# DRS4_GPIO_EXPANDER.net
KiCad netlist of a schematic drawn in Altium Designer
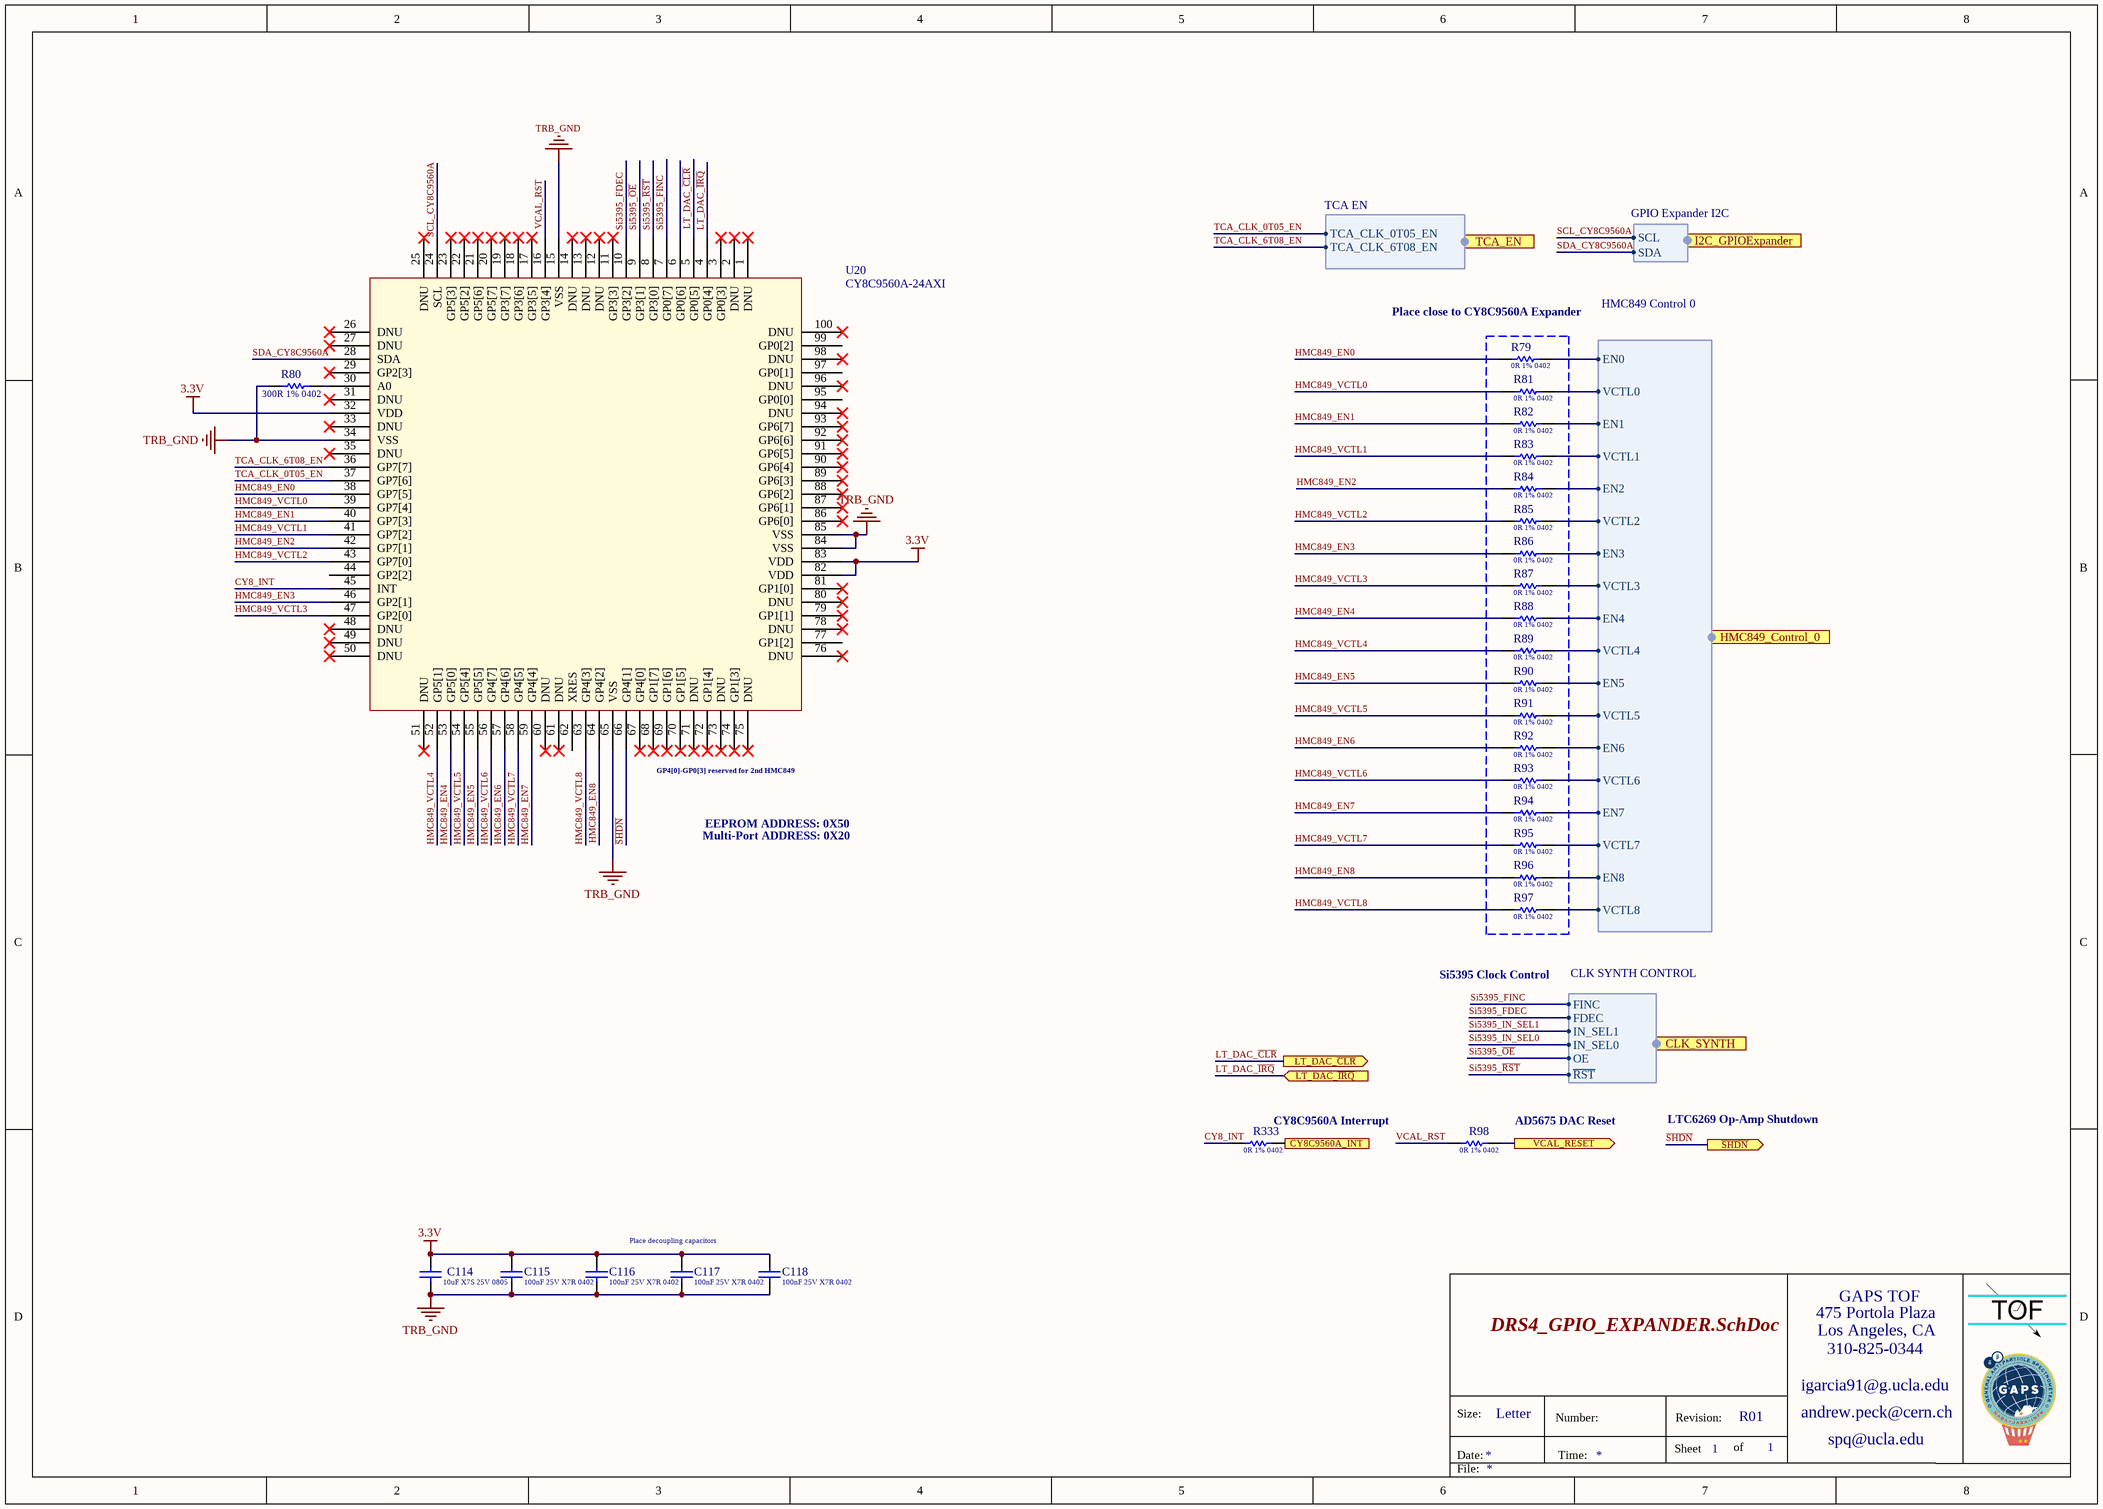
[diagram p0: DRS4_GPIO_EXPANDER.SchDoc]

(export (version "E")
  (design (tool "Eeschema 10.0.6"))
  (components
    (comp (ref "C114")
      (value "Cap_Murata_ GRM21BC71E106ME11L_10uF")
      (footprint "Cap_Murata_ GRM21BC71E106ME11L_10uF")
      (description "CAP CER 10uF 25V X7R 0805")
      (fields (field (name "CAPACITANCE") "10uF X7S 25V 0805"))
      (libsource (lib "Cap_Murata_ GRM21BC71E106ME11L_10uF") (part "Cap_Murata_ GRM21BC71E106ME11L_10uF"))
    )
    (comp (ref "C115")
      (value "Cap_Taiyo_Yuden_TMK105B7104KV-FR_100nF")
      (footprint "Cap_Taiyo_Yuden_TMK105B7104KV-FR_100nF")
      (description "CAP CER 100nF 25V X7R 0402")
      (fields (field (name "CAPACITANCE") "100nF 25V X7R 0402"))
      (libsource (lib "Cap_Taiyo_Yuden_TMK105B7104KV-FR_100nF") (part "Cap_Taiyo_Yuden_TMK105B7104KV-FR_100nF"))
    )
    (comp (ref "C116")
      (value "Cap_Taiyo_Yuden_TMK105B7104KV-FR_100nF")
      (footprint "Cap_Taiyo_Yuden_TMK105B7104KV-FR_100nF")
      (description "CAP CER 100nF 25V X7R 0402")
      (fields (field (name "CAPACITANCE") "100nF 25V X7R 0402"))
      (libsource (lib "Cap_Taiyo_Yuden_TMK105B7104KV-FR_100nF") (part "Cap_Taiyo_Yuden_TMK105B7104KV-FR_100nF"))
    )
    (comp (ref "C117")
      (value "Cap_Taiyo_Yuden_TMK105B7104KV-FR_100nF")
      (footprint "Cap_Taiyo_Yuden_TMK105B7104KV-FR_100nF")
      (description "CAP CER 100nF 25V X7R 0402")
      (fields (field (name "CAPACITANCE") "100nF 25V X7R 0402"))
      (libsource (lib "Cap_Taiyo_Yuden_TMK105B7104KV-FR_100nF") (part "Cap_Taiyo_Yuden_TMK105B7104KV-FR_100nF"))
    )
    (comp (ref "C118")
      (value "Cap_Taiyo_Yuden_TMK105B7104KV-FR_100nF")
      (footprint "Cap_Taiyo_Yuden_TMK105B7104KV-FR_100nF")
      (description "CAP CER 100nF 25V X7R 0402")
      (fields (field (name "CAPACITANCE") "100nF 25V X7R 0402"))
      (libsource (lib "Cap_Taiyo_Yuden_TMK105B7104KV-FR_100nF") (part "Cap_Taiyo_Yuden_TMK105B7104KV-FR_100nF"))
    )
    (comp (ref "R79")
      (value "Res_Vishay_CRCW04020000Z0EDC_0_Ohm")
      (footprint "Res_Vishay_CRCW04020000Z0EDC_0_Ohm")
      (description "0R 0.062W 1% 0402 (1005 Metric)  SMD")
      (fields (field (name "RESISTANCE") "0R 1% 0402"))
      (libsource (lib "Res_Vishay_CRCW04020000Z0EDC_0_Ohm") (part "Res_Vishay_CRCW04020000Z0EDC_0_Ohm"))
    )
    (comp (ref "R80")
      (value "300R 1% 0402")
      (footprint "RESC0402(1005)_L")
      (description "300R 0.063W 1% 0402 (1005 Metric)  SMD")
      (fields (field (name "TOLERANCE") "1 %") (field (name "POWER") "0.063 W"))
      (libsource (lib "Altium Content Vault") (part "RES"))
    )
    (comp (ref "R81")
      (value "Res_Vishay_CRCW04020000Z0EDC_0_Ohm")
      (footprint "Res_Vishay_CRCW04020000Z0EDC_0_Ohm")
      (description "0R 0.062W 1% 0402 (1005 Metric)  SMD")
      (fields (field (name "RESISTANCE") "0R 1% 0402"))
      (libsource (lib "Res_Vishay_CRCW04020000Z0EDC_0_Ohm") (part "Res_Vishay_CRCW04020000Z0EDC_0_Ohm"))
    )
    (comp (ref "R82")
      (value "Res_Vishay_CRCW04020000Z0EDC_0_Ohm")
      (footprint "Res_Vishay_CRCW04020000Z0EDC_0_Ohm")
      (description "0R 0.062W 1% 0402 (1005 Metric)  SMD")
      (fields (field (name "RESISTANCE") "0R 1% 0402"))
      (libsource (lib "Res_Vishay_CRCW04020000Z0EDC_0_Ohm") (part "Res_Vishay_CRCW04020000Z0EDC_0_Ohm"))
    )
    (comp (ref "R83")
      (value "Res_Vishay_CRCW04020000Z0EDC_0_Ohm")
      (footprint "Res_Vishay_CRCW04020000Z0EDC_0_Ohm")
      (description "0R 0.062W 1% 0402 (1005 Metric)  SMD")
      (fields (field (name "RESISTANCE") "0R 1% 0402"))
      (libsource (lib "Res_Vishay_CRCW04020000Z0EDC_0_Ohm") (part "Res_Vishay_CRCW04020000Z0EDC_0_Ohm"))
    )
    (comp (ref "R84")
      (value "Res_Vishay_CRCW04020000Z0EDC_0_Ohm")
      (footprint "Res_Vishay_CRCW04020000Z0EDC_0_Ohm")
      (description "0R 0.062W 1% 0402 (1005 Metric)  SMD")
      (fields (field (name "RESISTANCE") "0R 1% 0402"))
      (libsource (lib "Res_Vishay_CRCW04020000Z0EDC_0_Ohm") (part "Res_Vishay_CRCW04020000Z0EDC_0_Ohm"))
    )
    (comp (ref "R85")
      (value "Res_Vishay_CRCW04020000Z0EDC_0_Ohm")
      (footprint "Res_Vishay_CRCW04020000Z0EDC_0_Ohm")
      (description "0R 0.062W 1% 0402 (1005 Metric)  SMD")
      (fields (field (name "RESISTANCE") "0R 1% 0402"))
      (libsource (lib "Res_Vishay_CRCW04020000Z0EDC_0_Ohm") (part "Res_Vishay_CRCW04020000Z0EDC_0_Ohm"))
    )
    (comp (ref "R86")
      (value "Res_Vishay_CRCW04020000Z0EDC_0_Ohm")
      (footprint "Res_Vishay_CRCW04020000Z0EDC_0_Ohm")
      (description "0R 0.062W 1% 0402 (1005 Metric)  SMD")
      (fields (field (name "RESISTANCE") "0R 1% 0402"))
      (libsource (lib "Res_Vishay_CRCW04020000Z0EDC_0_Ohm") (part "Res_Vishay_CRCW04020000Z0EDC_0_Ohm"))
    )
    (comp (ref "R87")
      (value "Res_Vishay_CRCW04020000Z0EDC_0_Ohm")
      (footprint "Res_Vishay_CRCW04020000Z0EDC_0_Ohm")
      (description "0R 0.062W 1% 0402 (1005 Metric)  SMD")
      (fields (field (name "RESISTANCE") "0R 1% 0402"))
      (libsource (lib "Res_Vishay_CRCW04020000Z0EDC_0_Ohm") (part "Res_Vishay_CRCW04020000Z0EDC_0_Ohm"))
    )
    (comp (ref "R88")
      (value "Res_Vishay_CRCW04020000Z0EDC_0_Ohm")
      (footprint "Res_Vishay_CRCW04020000Z0EDC_0_Ohm")
      (description "0R 0.062W 1% 0402 (1005 Metric)  SMD")
      (fields (field (name "RESISTANCE") "0R 1% 0402"))
      (libsource (lib "Res_Vishay_CRCW04020000Z0EDC_0_Ohm") (part "Res_Vishay_CRCW04020000Z0EDC_0_Ohm"))
    )
    (comp (ref "R89")
      (value "Res_Vishay_CRCW04020000Z0EDC_0_Ohm")
      (footprint "Res_Vishay_CRCW04020000Z0EDC_0_Ohm")
      (description "0R 0.062W 1% 0402 (1005 Metric)  SMD")
      (fields (field (name "RESISTANCE") "0R 1% 0402"))
      (libsource (lib "Res_Vishay_CRCW04020000Z0EDC_0_Ohm") (part "Res_Vishay_CRCW04020000Z0EDC_0_Ohm"))
    )
    (comp (ref "R90")
      (value "Res_Vishay_CRCW04020000Z0EDC_0_Ohm")
      (footprint "Res_Vishay_CRCW04020000Z0EDC_0_Ohm")
      (description "0R 0.062W 1% 0402 (1005 Metric)  SMD")
      (fields (field (name "RESISTANCE") "0R 1% 0402"))
      (libsource (lib "Res_Vishay_CRCW04020000Z0EDC_0_Ohm") (part "Res_Vishay_CRCW04020000Z0EDC_0_Ohm"))
    )
    (comp (ref "R91")
      (value "Res_Vishay_CRCW04020000Z0EDC_0_Ohm")
      (footprint "Res_Vishay_CRCW04020000Z0EDC_0_Ohm")
      (description "0R 0.062W 1% 0402 (1005 Metric)  SMD")
      (fields (field (name "RESISTANCE") "0R 1% 0402"))
      (libsource (lib "Res_Vishay_CRCW04020000Z0EDC_0_Ohm") (part "Res_Vishay_CRCW04020000Z0EDC_0_Ohm"))
    )
    (comp (ref "R92")
      (value "Res_Vishay_CRCW04020000Z0EDC_0_Ohm")
      (footprint "Res_Vishay_CRCW04020000Z0EDC_0_Ohm")
      (description "0R 0.062W 1% 0402 (1005 Metric)  SMD")
      (fields (field (name "RESISTANCE") "0R 1% 0402"))
      (libsource (lib "Res_Vishay_CRCW04020000Z0EDC_0_Ohm") (part "Res_Vishay_CRCW04020000Z0EDC_0_Ohm"))
    )
    (comp (ref "R93")
      (value "Res_Vishay_CRCW04020000Z0EDC_0_Ohm")
      (footprint "Res_Vishay_CRCW04020000Z0EDC_0_Ohm")
      (description "0R 0.062W 1% 0402 (1005 Metric)  SMD")
      (fields (field (name "RESISTANCE") "0R 1% 0402"))
      (libsource (lib "Res_Vishay_CRCW04020000Z0EDC_0_Ohm") (part "Res_Vishay_CRCW04020000Z0EDC_0_Ohm"))
    )
    (comp (ref "R94")
      (value "Res_Vishay_CRCW04020000Z0EDC_0_Ohm")
      (footprint "Res_Vishay_CRCW04020000Z0EDC_0_Ohm")
      (description "0R 0.062W 1% 0402 (1005 Metric)  SMD")
      (fields (field (name "RESISTANCE") "0R 1% 0402"))
      (libsource (lib "Res_Vishay_CRCW04020000Z0EDC_0_Ohm") (part "Res_Vishay_CRCW04020000Z0EDC_0_Ohm"))
    )
    (comp (ref "R95")
      (value "Res_Vishay_CRCW04020000Z0EDC_0_Ohm")
      (footprint "Res_Vishay_CRCW04020000Z0EDC_0_Ohm")
      (description "0R 0.062W 1% 0402 (1005 Metric)  SMD")
      (fields (field (name "RESISTANCE") "0R 1% 0402"))
      (libsource (lib "Res_Vishay_CRCW04020000Z0EDC_0_Ohm") (part "Res_Vishay_CRCW04020000Z0EDC_0_Ohm"))
    )
    (comp (ref "R96")
      (value "Res_Vishay_CRCW04020000Z0EDC_0_Ohm")
      (footprint "Res_Vishay_CRCW04020000Z0EDC_0_Ohm")
      (description "0R 0.062W 1% 0402 (1005 Metric)  SMD")
      (fields (field (name "RESISTANCE") "0R 1% 0402"))
      (libsource (lib "Res_Vishay_CRCW04020000Z0EDC_0_Ohm") (part "Res_Vishay_CRCW04020000Z0EDC_0_Ohm"))
    )
    (comp (ref "R97")
      (value "Res_Vishay_CRCW04020000Z0EDC_0_Ohm")
      (footprint "Res_Vishay_CRCW04020000Z0EDC_0_Ohm")
      (description "0R 0.062W 1% 0402 (1005 Metric)  SMD")
      (fields (field (name "RESISTANCE") "0R 1% 0402"))
      (libsource (lib "Res_Vishay_CRCW04020000Z0EDC_0_Ohm") (part "Res_Vishay_CRCW04020000Z0EDC_0_Ohm"))
    )
    (comp (ref "R98")
      (value "Res_Vishay_CRCW04020000Z0EDC_0_Ohm")
      (footprint "Res_Vishay_CRCW04020000Z0EDC_0_Ohm")
      (description "0R 0.062W 1% 0402 (1005 Metric)  SMD")
      (fields (field (name "RESISTANCE") "0R 1% 0402"))
      (libsource (lib "Res_Vishay_CRCW04020000Z0EDC_0_Ohm") (part "Res_Vishay_CRCW04020000Z0EDC_0_Ohm"))
    )
    (comp (ref "R333")
      (value "Res_Vishay_CRCW04020000Z0EDC_0_Ohm")
      (footprint "Res_Vishay_CRCW04020000Z0EDC_0_Ohm")
      (description "0R 0.062W 1% 0402 (1005 Metric)  SMD")
      (fields (field (name "RESISTANCE") "0R 1% 0402"))
      (libsource (lib "Res_Vishay_CRCW04020000Z0EDC_0_Ohm") (part "Res_Vishay_CRCW04020000Z0EDC_0_Ohm"))
    )
    (comp (ref "U20")
      (value "IC_Cypress_Semiconductor_CY8C9560A-24AXI")
      (footprint "IC_Cypress_Semiconductor_CY8C9560A-24AXI")
      (description "Interface - I/O Expanders 60BIT IO EXPANDER W/EEPROM")
      (fields (field (name "SERIES") "CY8C9560A-24AXI"))
      (libsource (lib "IC_Cypress_Semiconductor_CY8C9560A-24AXI") (part "IC_Cypress_Semiconductor_CY8C9560A-24AXI"))
    )
  )
  (nets
    (net (code "12") (name "/CY8C9560A_INT") (class "Default")
      (node (ref "R333") (pin "1") (pinfunction "1_1") (pintype "passive"))
    )
    (net (code "13") (name "/CY8_INT") (class "Default")
      (node (ref "R333") (pin "2") (pinfunction "2_2") (pintype "passive"))
      (node (ref "U20") (pin "45") (pinfunction "INT_45") (pintype "passive"))
    )
    (net (code "14") (name "/EN0") (class "Default")
      (node (ref "R79") (pin "2") (pinfunction "2_2") (pintype "passive"))
    )
    (net (code "15") (name "/EN1") (class "Default")
      (node (ref "R82") (pin "2") (pinfunction "2_2") (pintype "passive"))
    )
    (net (code "16") (name "/EN2") (class "Default")
      (node (ref "R84") (pin "2") (pinfunction "2_2") (pintype "passive"))
    )
    (net (code "17") (name "/EN3") (class "Default")
      (node (ref "R86") (pin "2") (pinfunction "2_2") (pintype "passive"))
    )
    (net (code "18") (name "/EN4") (class "Default")
      (node (ref "R88") (pin "2") (pinfunction "2_2") (pintype "passive"))
    )
    (net (code "19") (name "/EN5") (class "Default")
      (node (ref "R90") (pin "2") (pinfunction "2_2") (pintype "passive"))
    )
    (net (code "20") (name "/EN6") (class "Default")
      (node (ref "R92") (pin "2") (pinfunction "2_2") (pintype "passive"))
    )
    (net (code "21") (name "/EN7") (class "Default")
      (node (ref "R94") (pin "2") (pinfunction "2_2") (pintype "passive"))
    )
    (net (code "22") (name "/EN8") (class "Default")
      (node (ref "R96") (pin "2") (pinfunction "2_2") (pintype "passive"))
    )
    (net (code "23") (name "/HMC849_EN0") (class "Default")
      (node (ref "R79") (pin "1") (pinfunction "1_1") (pintype "passive"))
      (node (ref "U20") (pin "38") (pinfunction "GP7[5]_38") (pintype "passive"))
    )
    (net (code "24") (name "/HMC849_EN1") (class "Default")
      (node (ref "R82") (pin "1") (pinfunction "1_1") (pintype "passive"))
      (node (ref "U20") (pin "40") (pinfunction "GP7[3]_40") (pintype "passive"))
    )
    (net (code "25") (name "/HMC849_EN2") (class "Default")
      (node (ref "R84") (pin "1") (pinfunction "1_1") (pintype "passive"))
      (node (ref "U20") (pin "42") (pinfunction "GP7[1]_42") (pintype "passive"))
    )
    (net (code "26") (name "/HMC849_EN3") (class "Default")
      (node (ref "R86") (pin "1") (pinfunction "1_1") (pintype "passive"))
      (node (ref "U20") (pin "46") (pinfunction "GP2[1]_46") (pintype "passive"))
    )
    (net (code "27") (name "/HMC849_EN4") (class "Default")
      (node (ref "R88") (pin "1") (pinfunction "1_1") (pintype "passive"))
      (node (ref "U20") (pin "53") (pinfunction "GP5[0]_53") (pintype "passive"))
    )
    (net (code "28") (name "/HMC849_EN5") (class "Default")
      (node (ref "R90") (pin "1") (pinfunction "1_1") (pintype "passive"))
      (node (ref "U20") (pin "55") (pinfunction "GP5[5]_55") (pintype "passive"))
    )
    (net (code "29") (name "/HMC849_EN6") (class "Default")
      (node (ref "R92") (pin "1") (pinfunction "1_1") (pintype "passive"))
      (node (ref "U20") (pin "57") (pinfunction "GP4[6]_57") (pintype "passive"))
    )
    (net (code "30") (name "/HMC849_EN7") (class "Default")
      (node (ref "R94") (pin "1") (pinfunction "1_1") (pintype "passive"))
      (node (ref "U20") (pin "59") (pinfunction "GP4[4]_59") (pintype "passive"))
    )
    (net (code "31") (name "/HMC849_EN8") (class "Default")
      (node (ref "R96") (pin "1") (pinfunction "1_1") (pintype "passive"))
      (node (ref "U20") (pin "64") (pinfunction "GP4[2]_64") (pintype "passive"))
    )
    (net (code "32") (name "/HMC849_VCTL0") (class "Default")
      (node (ref "R81") (pin "1") (pinfunction "1_1") (pintype "passive"))
      (node (ref "U20") (pin "39") (pinfunction "GP7[4]_39") (pintype "passive"))
    )
    (net (code "33") (name "/HMC849_VCTL1") (class "Default")
      (node (ref "R83") (pin "1") (pinfunction "1_1") (pintype "passive"))
      (node (ref "U20") (pin "41") (pinfunction "GP7[2]_41") (pintype "passive"))
    )
    (net (code "34") (name "/HMC849_VCTL2") (class "Default")
      (node (ref "R85") (pin "1") (pinfunction "1_1") (pintype "passive"))
      (node (ref "U20") (pin "43") (pinfunction "GP7[0]_43") (pintype "passive"))
    )
    (net (code "35") (name "/HMC849_VCTL3") (class "Default")
      (node (ref "R87") (pin "1") (pinfunction "1_1") (pintype "passive"))
      (node (ref "U20") (pin "47") (pinfunction "GP2[0]_47") (pintype "passive"))
    )
    (net (code "36") (name "/HMC849_VCTL4") (class "Default")
      (node (ref "R89") (pin "1") (pinfunction "1_1") (pintype "passive"))
      (node (ref "U20") (pin "52") (pinfunction "GP5[1]_52") (pintype "passive"))
    )
    (net (code "37") (name "/HMC849_VCTL5") (class "Default")
      (node (ref "R91") (pin "1") (pinfunction "1_1") (pintype "passive"))
      (node (ref "U20") (pin "54") (pinfunction "GP5[4]_54") (pintype "passive"))
    )
    (net (code "38") (name "/HMC849_VCTL6") (class "Default")
      (node (ref "R93") (pin "1") (pinfunction "1_1") (pintype "passive"))
      (node (ref "U20") (pin "56") (pinfunction "GP4[7]_56") (pintype "passive"))
    )
    (net (code "39") (name "/HMC849_VCTL7") (class "Default")
      (node (ref "R95") (pin "1") (pinfunction "1_1") (pintype "passive"))
      (node (ref "U20") (pin "58") (pinfunction "GP4[5]_58") (pintype "passive"))
    )
    (net (code "40") (name "/HMC849_VCTL8") (class "Default")
      (node (ref "R97") (pin "1") (pinfunction "1_1") (pintype "passive"))
      (node (ref "U20") (pin "63") (pinfunction "GP4[3]_63") (pintype "passive"))
    )
    (net (code "41") (name "/LT_DAC_~{CLR}") (class "Default")
      (node (ref "U20") (pin "5") (pinfunction "GP0[5]_5") (pintype "passive"))
    )
    (net (code "42") (name "/LT_DAC_~{IRQ}") (class "Default")
      (node (ref "U20") (pin "4") (pinfunction "GP0[4]_4") (pintype "passive"))
    )
    (net (code "43") (name "/SCL_CY8C9560A") (class "Default")
      (node (ref "U20") (pin "24") (pinfunction "SCL_24") (pintype "passive"))
    )
    (net (code "44") (name "/SDA_CY8C9560A") (class "Default")
      (node (ref "U20") (pin "28") (pinfunction "SDA_28") (pintype "passive"))
    )
    (net (code "45") (name "/Si5395_FDEC") (class "Default")
      (node (ref "U20") (pin "10") (pinfunction "GP3[2]_10") (pintype "passive"))
    )
    (net (code "46") (name "/Si5395_FINC") (class "Default")
      (node (ref "U20") (pin "7") (pinfunction "GP0[7]_7") (pintype "passive"))
    )
    (net (code "49") (name "/Si5395_~{OE}") (class "Default")
      (node (ref "U20") (pin "9") (pinfunction "GP3[1]_9") (pintype "passive"))
    )
    (net (code "50") (name "/Si5395_~{RST}") (class "Default")
      (node (ref "U20") (pin "8") (pinfunction "GP3[0]_8") (pintype "passive"))
    )
    (net (code "51") (name "/TCA_CLK_0T05_EN") (class "Default")
      (node (ref "U20") (pin "37") (pinfunction "GP7[6]_37") (pintype "passive"))
    )
    (net (code "52") (name "/TCA_CLK_6T08_EN") (class "Default")
      (node (ref "U20") (pin "36") (pinfunction "GP7[7]_36") (pintype "passive"))
    )
    (net (code "53") (name "/VCAL_RESET") (class "Default")
      (node (ref "R98") (pin "1") (pinfunction "1_1") (pintype "passive"))
    )
    (net (code "54") (name "/VCAL_RST") (class "Default")
      (node (ref "R98") (pin "2") (pinfunction "2_2") (pintype "passive"))
      (node (ref "U20") (pin "16") (pinfunction "GP3[4]_16") (pintype "passive"))
    )
    (net (code "55") (name "/VCTL0") (class "Default")
      (node (ref "R81") (pin "2") (pinfunction "2_2") (pintype "passive"))
    )
    (net (code "56") (name "/VCTL1") (class "Default")
      (node (ref "R83") (pin "2") (pinfunction "2_2") (pintype "passive"))
    )
    (net (code "57") (name "/VCTL2") (class "Default")
      (node (ref "R85") (pin "2") (pinfunction "2_2") (pintype "passive"))
    )
    (net (code "58") (name "/VCTL3") (class "Default")
      (node (ref "R87") (pin "2") (pinfunction "2_2") (pintype "passive"))
    )
    (net (code "59") (name "/VCTL4") (class "Default")
      (node (ref "R89") (pin "2") (pinfunction "2_2") (pintype "passive"))
    )
    (net (code "60") (name "/VCTL5") (class "Default")
      (node (ref "R91") (pin "2") (pinfunction "2_2") (pintype "passive"))
    )
    (net (code "61") (name "/VCTL6") (class "Default")
      (node (ref "R93") (pin "2") (pinfunction "2_2") (pintype "passive"))
    )
    (net (code "62") (name "/VCTL7") (class "Default")
      (node (ref "R95") (pin "2") (pinfunction "2_2") (pintype "passive"))
    )
    (net (code "63") (name "/VCTL8") (class "Default")
      (node (ref "R97") (pin "2") (pinfunction "2_2") (pintype "passive"))
    )
    (net (code "68") (name "/~{SHDN}") (class "Default")
      (node (ref "U20") (pin "66") (pinfunction "GP4[1]_66") (pintype "passive"))
    )
    (net (code "69") (name "3.3V") (class "Default")
      (node (ref "C114") (pin "1") (pinfunction "1_1") (pintype "passive"))
      (node (ref "C115") (pin "2") (pinfunction "2_2") (pintype "passive"))
      (node (ref "C116") (pin "2") (pinfunction "2_2") (pintype "passive"))
      (node (ref "C117") (pin "2") (pinfunction "2_2") (pintype "passive"))
      (node (ref "C118") (pin "2") (pinfunction "2_2") (pintype "passive"))
      (node (ref "U20") (pin "32") (pinfunction "VDD_32") (pintype "passive"))
      (node (ref "U20") (pin "82") (pinfunction "VDD_82") (pintype "passive"))
      (node (ref "U20") (pin "83") (pinfunction "VDD_83") (pintype "passive"))
    )
    (net (code "70") (name "Net-(U20-A0)") (class "Default")
      (node (ref "R80") (pin "1") (pinfunction "1_1") (pintype "passive"))
      (node (ref "U20") (pin "30") (pinfunction "A0_30") (pintype "passive"))
    )
    (net (code "71") (name "TRB_GND") (class "Default")
      (node (ref "C114") (pin "2") (pinfunction "2_2") (pintype "passive"))
      (node (ref "C115") (pin "1") (pinfunction "1_1") (pintype "passive"))
      (node (ref "C116") (pin "1") (pinfunction "1_1") (pintype "passive"))
      (node (ref "C117") (pin "1") (pinfunction "1_1") (pintype "passive"))
      (node (ref "C118") (pin "1") (pinfunction "1_1") (pintype "passive"))
      (node (ref "R80") (pin "2") (pinfunction "2_2") (pintype "passive"))
      (node (ref "U20") (pin "15") (pinfunction "VSS_15") (pintype "passive"))
      (node (ref "U20") (pin "34") (pinfunction "VSS_34") (pintype "passive"))
      (node (ref "U20") (pin "65") (pinfunction "VSS_65") (pintype "passive"))
      (node (ref "U20") (pin "84") (pinfunction "VSS_84") (pintype "passive"))
      (node (ref "U20") (pin "85") (pinfunction "VSS_85") (pintype "passive"))
    )
    (net (code "72") (name "unconnected-(U20-DNU-Pad1)") (class "Default")
      (node (ref "U20") (pin "1") (pinfunction "DNU_1") (pintype "passive+no_connect"))
    )
    (net (code "73") (name "unconnected-(U20-DNU-Pad2)") (class "Default")
      (node (ref "U20") (pin "2") (pinfunction "DNU_2") (pintype "passive+no_connect"))
    )
    (net (code "74") (name "unconnected-(U20-DNU-Pad12)") (class "Default")
      (node (ref "U20") (pin "12") (pinfunction "DNU_12") (pintype "passive+no_connect"))
    )
    (net (code "75") (name "unconnected-(U20-DNU-Pad13)") (class "Default")
      (node (ref "U20") (pin "13") (pinfunction "DNU_13") (pintype "passive+no_connect"))
    )
    (net (code "76") (name "unconnected-(U20-DNU-Pad14)") (class "Default")
      (node (ref "U20") (pin "14") (pinfunction "DNU_14") (pintype "passive+no_connect"))
    )
    (net (code "77") (name "unconnected-(U20-DNU-Pad25)") (class "Default")
      (node (ref "U20") (pin "25") (pinfunction "DNU_25") (pintype "passive+no_connect"))
    )
    (net (code "78") (name "unconnected-(U20-DNU-Pad26)") (class "Default")
      (node (ref "U20") (pin "26") (pinfunction "DNU_26") (pintype "passive+no_connect"))
    )
    (net (code "79") (name "unconnected-(U20-DNU-Pad27)") (class "Default")
      (node (ref "U20") (pin "27") (pinfunction "DNU_27") (pintype "passive+no_connect"))
    )
    (net (code "80") (name "unconnected-(U20-DNU-Pad31)") (class "Default")
      (node (ref "U20") (pin "31") (pinfunction "DNU_31") (pintype "passive+no_connect"))
    )
    (net (code "81") (name "unconnected-(U20-DNU-Pad33)") (class "Default")
      (node (ref "U20") (pin "33") (pinfunction "DNU_33") (pintype "passive+no_connect"))
    )
    (net (code "82") (name "unconnected-(U20-DNU-Pad35)") (class "Default")
      (node (ref "U20") (pin "35") (pinfunction "DNU_35") (pintype "passive+no_connect"))
    )
    (net (code "83") (name "unconnected-(U20-DNU-Pad48)") (class "Default")
      (node (ref "U20") (pin "48") (pinfunction "DNU_48") (pintype "passive+no_connect"))
    )
    (net (code "84") (name "unconnected-(U20-DNU-Pad49)") (class "Default")
      (node (ref "U20") (pin "49") (pinfunction "DNU_49") (pintype "passive+no_connect"))
    )
    (net (code "85") (name "unconnected-(U20-DNU-Pad50)") (class "Default")
      (node (ref "U20") (pin "50") (pinfunction "DNU_50") (pintype "passive+no_connect"))
    )
    (net (code "86") (name "unconnected-(U20-DNU-Pad51)") (class "Default")
      (node (ref "U20") (pin "51") (pinfunction "DNU_51") (pintype "passive+no_connect"))
    )
    (net (code "87") (name "unconnected-(U20-DNU-Pad60)") (class "Default")
      (node (ref "U20") (pin "60") (pinfunction "DNU_60") (pintype "passive+no_connect"))
    )
    (net (code "88") (name "unconnected-(U20-DNU-Pad61)") (class "Default")
      (node (ref "U20") (pin "61") (pinfunction "DNU_61") (pintype "passive+no_connect"))
    )
    (net (code "89") (name "unconnected-(U20-DNU-Pad71)") (class "Default")
      (node (ref "U20") (pin "71") (pinfunction "DNU_71") (pintype "passive+no_connect"))
    )
    (net (code "90") (name "unconnected-(U20-DNU-Pad73)") (class "Default")
      (node (ref "U20") (pin "73") (pinfunction "DNU_73") (pintype "passive+no_connect"))
    )
    (net (code "91") (name "unconnected-(U20-DNU-Pad75)") (class "Default")
      (node (ref "U20") (pin "75") (pinfunction "DNU_75") (pintype "passive+no_connect"))
    )
    (net (code "92") (name "unconnected-(U20-DNU-Pad76)") (class "Default")
      (node (ref "U20") (pin "76") (pinfunction "DNU_76") (pintype "passive+no_connect"))
    )
    (net (code "93") (name "unconnected-(U20-DNU-Pad78)") (class "Default")
      (node (ref "U20") (pin "78") (pinfunction "DNU_78") (pintype "passive+no_connect"))
    )
    (net (code "94") (name "unconnected-(U20-DNU-Pad80)") (class "Default")
      (node (ref "U20") (pin "80") (pinfunction "DNU_80") (pintype "passive+no_connect"))
    )
    (net (code "95") (name "unconnected-(U20-DNU-Pad94)") (class "Default")
      (node (ref "U20") (pin "94") (pinfunction "DNU_94") (pintype "passive+no_connect"))
    )
    (net (code "96") (name "unconnected-(U20-DNU-Pad96)") (class "Default")
      (node (ref "U20") (pin "96") (pinfunction "DNU_96") (pintype "passive+no_connect"))
    )
    (net (code "97") (name "unconnected-(U20-DNU-Pad98)") (class "Default")
      (node (ref "U20") (pin "98") (pinfunction "DNU_98") (pintype "passive+no_connect"))
    )
    (net (code "98") (name "unconnected-(U20-DNU-Pad100)") (class "Default")
      (node (ref "U20") (pin "100") (pinfunction "DNU_100") (pintype "passive+no_connect"))
    )
    (net (code "99") (name "unconnected-(U20-GP0[0]-Pad95)") (class "Default")
      (node (ref "U20") (pin "95") (pinfunction "GP0[0]_95") (pintype "passive"))
    )
    (net (code "100") (name "unconnected-(U20-GP0[1]-Pad97)") (class "Default")
      (node (ref "U20") (pin "97") (pinfunction "GP0[1]_97") (pintype "passive"))
    )
    (net (code "101") (name "unconnected-(U20-GP0[2]-Pad99)") (class "Default")
      (node (ref "U20") (pin "99") (pinfunction "GP0[2]_99") (pintype "passive"))
    )
    (net (code "102") (name "unconnected-(U20-GP0[3]-Pad3)") (class "Default")
      (node (ref "U20") (pin "3") (pinfunction "GP0[3]_3") (pintype "passive+no_connect"))
    )
    (net (code "103") (name "unconnected-(U20-GP0[6]-Pad6)") (class "Default")
      (node (ref "U20") (pin "6") (pinfunction "GP0[6]_6") (pintype "passive"))
    )
    (net (code "104") (name "unconnected-(U20-GP1[0]-Pad81)") (class "Default")
      (node (ref "U20") (pin "81") (pinfunction "GP1[0]_81") (pintype "passive+no_connect"))
    )
    (net (code "105") (name "unconnected-(U20-GP1[1]-Pad79)") (class "Default")
      (node (ref "U20") (pin "79") (pinfunction "GP1[1]_79") (pintype "passive+no_connect"))
    )
    (net (code "106") (name "unconnected-(U20-GP1[2]-Pad77)") (class "Default")
      (node (ref "U20") (pin "77") (pinfunction "GP1[2]_77") (pintype "passive"))
    )
    (net (code "107") (name "unconnected-(U20-GP1[3]-Pad74)") (class "Default")
      (node (ref "U20") (pin "74") (pinfunction "GP1[3]_74") (pintype "passive+no_connect"))
    )
    (net (code "108") (name "unconnected-(U20-GP1[4]-Pad72)") (class "Default")
      (node (ref "U20") (pin "72") (pinfunction "GP1[4]_72") (pintype "passive+no_connect"))
    )
    (net (code "109") (name "unconnected-(U20-GP1[5]-Pad70)") (class "Default")
      (node (ref "U20") (pin "70") (pinfunction "GP1[5]_70") (pintype "passive+no_connect"))
    )
    (net (code "110") (name "unconnected-(U20-GP1[6]-Pad69)") (class "Default")
      (node (ref "U20") (pin "69") (pinfunction "GP1[6]_69") (pintype "passive+no_connect"))
    )
    (net (code "111") (name "unconnected-(U20-GP1[7]-Pad68)") (class "Default")
      (node (ref "U20") (pin "68") (pinfunction "GP1[7]_68") (pintype "passive+no_connect"))
    )
    (net (code "112") (name "unconnected-(U20-GP2[2]-Pad44)") (class "Default")
      (node (ref "U20") (pin "44") (pinfunction "GP2[2]_44") (pintype "passive"))
    )
    (net (code "113") (name "unconnected-(U20-GP2[3]-Pad29)") (class "Default")
      (node (ref "U20") (pin "29") (pinfunction "GP2[3]_29") (pintype "passive+no_connect"))
    )
    (net (code "114") (name "unconnected-(U20-GP3[3]-Pad11)") (class "Default")
      (node (ref "U20") (pin "11") (pinfunction "GP3[3]_11") (pintype "passive+no_connect"))
    )
    (net (code "115") (name "unconnected-(U20-GP3[5]-Pad17)") (class "Default")
      (node (ref "U20") (pin "17") (pinfunction "GP3[5]_17") (pintype "passive+no_connect"))
    )
    (net (code "116") (name "unconnected-(U20-GP3[6]-Pad18)") (class "Default")
      (node (ref "U20") (pin "18") (pinfunction "GP3[6]_18") (pintype "passive+no_connect"))
    )
    (net (code "117") (name "unconnected-(U20-GP3[7]-Pad19)") (class "Default")
      (node (ref "U20") (pin "19") (pinfunction "GP3[7]_19") (pintype "passive+no_connect"))
    )
    (net (code "118") (name "unconnected-(U20-GP4[0]-Pad67)") (class "Default")
      (node (ref "U20") (pin "67") (pinfunction "GP4[0]_67") (pintype "passive+no_connect"))
    )
    (net (code "119") (name "unconnected-(U20-GP5[2]-Pad22)") (class "Default")
      (node (ref "U20") (pin "22") (pinfunction "GP5[2]_22") (pintype "passive+no_connect"))
    )
    (net (code "120") (name "unconnected-(U20-GP5[3]-Pad23)") (class "Default")
      (node (ref "U20") (pin "23") (pinfunction "GP5[3]_23") (pintype "passive+no_connect"))
    )
    (net (code "121") (name "unconnected-(U20-GP5[6]-Pad21)") (class "Default")
      (node (ref "U20") (pin "21") (pinfunction "GP5[6]_21") (pintype "passive+no_connect"))
    )
    (net (code "122") (name "unconnected-(U20-GP5[7]-Pad20)") (class "Default")
      (node (ref "U20") (pin "20") (pinfunction "GP5[7]_20") (pintype "passive+no_connect"))
    )
    (net (code "123") (name "unconnected-(U20-GP6[0]-Pad86)") (class "Default")
      (node (ref "U20") (pin "86") (pinfunction "GP6[0]_86") (pintype "passive+no_connect"))
    )
    (net (code "124") (name "unconnected-(U20-GP6[1]-Pad87)") (class "Default")
      (node (ref "U20") (pin "87") (pinfunction "GP6[1]_87") (pintype "passive+no_connect"))
    )
    (net (code "125") (name "unconnected-(U20-GP6[2]-Pad88)") (class "Default")
      (node (ref "U20") (pin "88") (pinfunction "GP6[2]_88") (pintype "passive+no_connect"))
    )
    (net (code "126") (name "unconnected-(U20-GP6[3]-Pad89)") (class "Default")
      (node (ref "U20") (pin "89") (pinfunction "GP6[3]_89") (pintype "passive+no_connect"))
    )
    (net (code "127") (name "unconnected-(U20-GP6[4]-Pad90)") (class "Default")
      (node (ref "U20") (pin "90") (pinfunction "GP6[4]_90") (pintype "passive+no_connect"))
    )
    (net (code "128") (name "unconnected-(U20-GP6[5]-Pad91)") (class "Default")
      (node (ref "U20") (pin "91") (pinfunction "GP6[5]_91") (pintype "passive+no_connect"))
    )
    (net (code "129") (name "unconnected-(U20-GP6[6]-Pad92)") (class "Default")
      (node (ref "U20") (pin "92") (pinfunction "GP6[6]_92") (pintype "passive+no_connect"))
    )
    (net (code "130") (name "unconnected-(U20-GP6[7]-Pad93)") (class "Default")
      (node (ref "U20") (pin "93") (pinfunction "GP6[7]_93") (pintype "passive+no_connect"))
    )
    (net (code "131") (name "unconnected-(U20-XRES-Pad62)") (class "Default")
      (node (ref "U20") (pin "62") (pinfunction "XRES_62") (pintype "passive"))
    )
  )
)
